# communication-hub.net
KiCad netlist of a schematic drawn in EAGLE
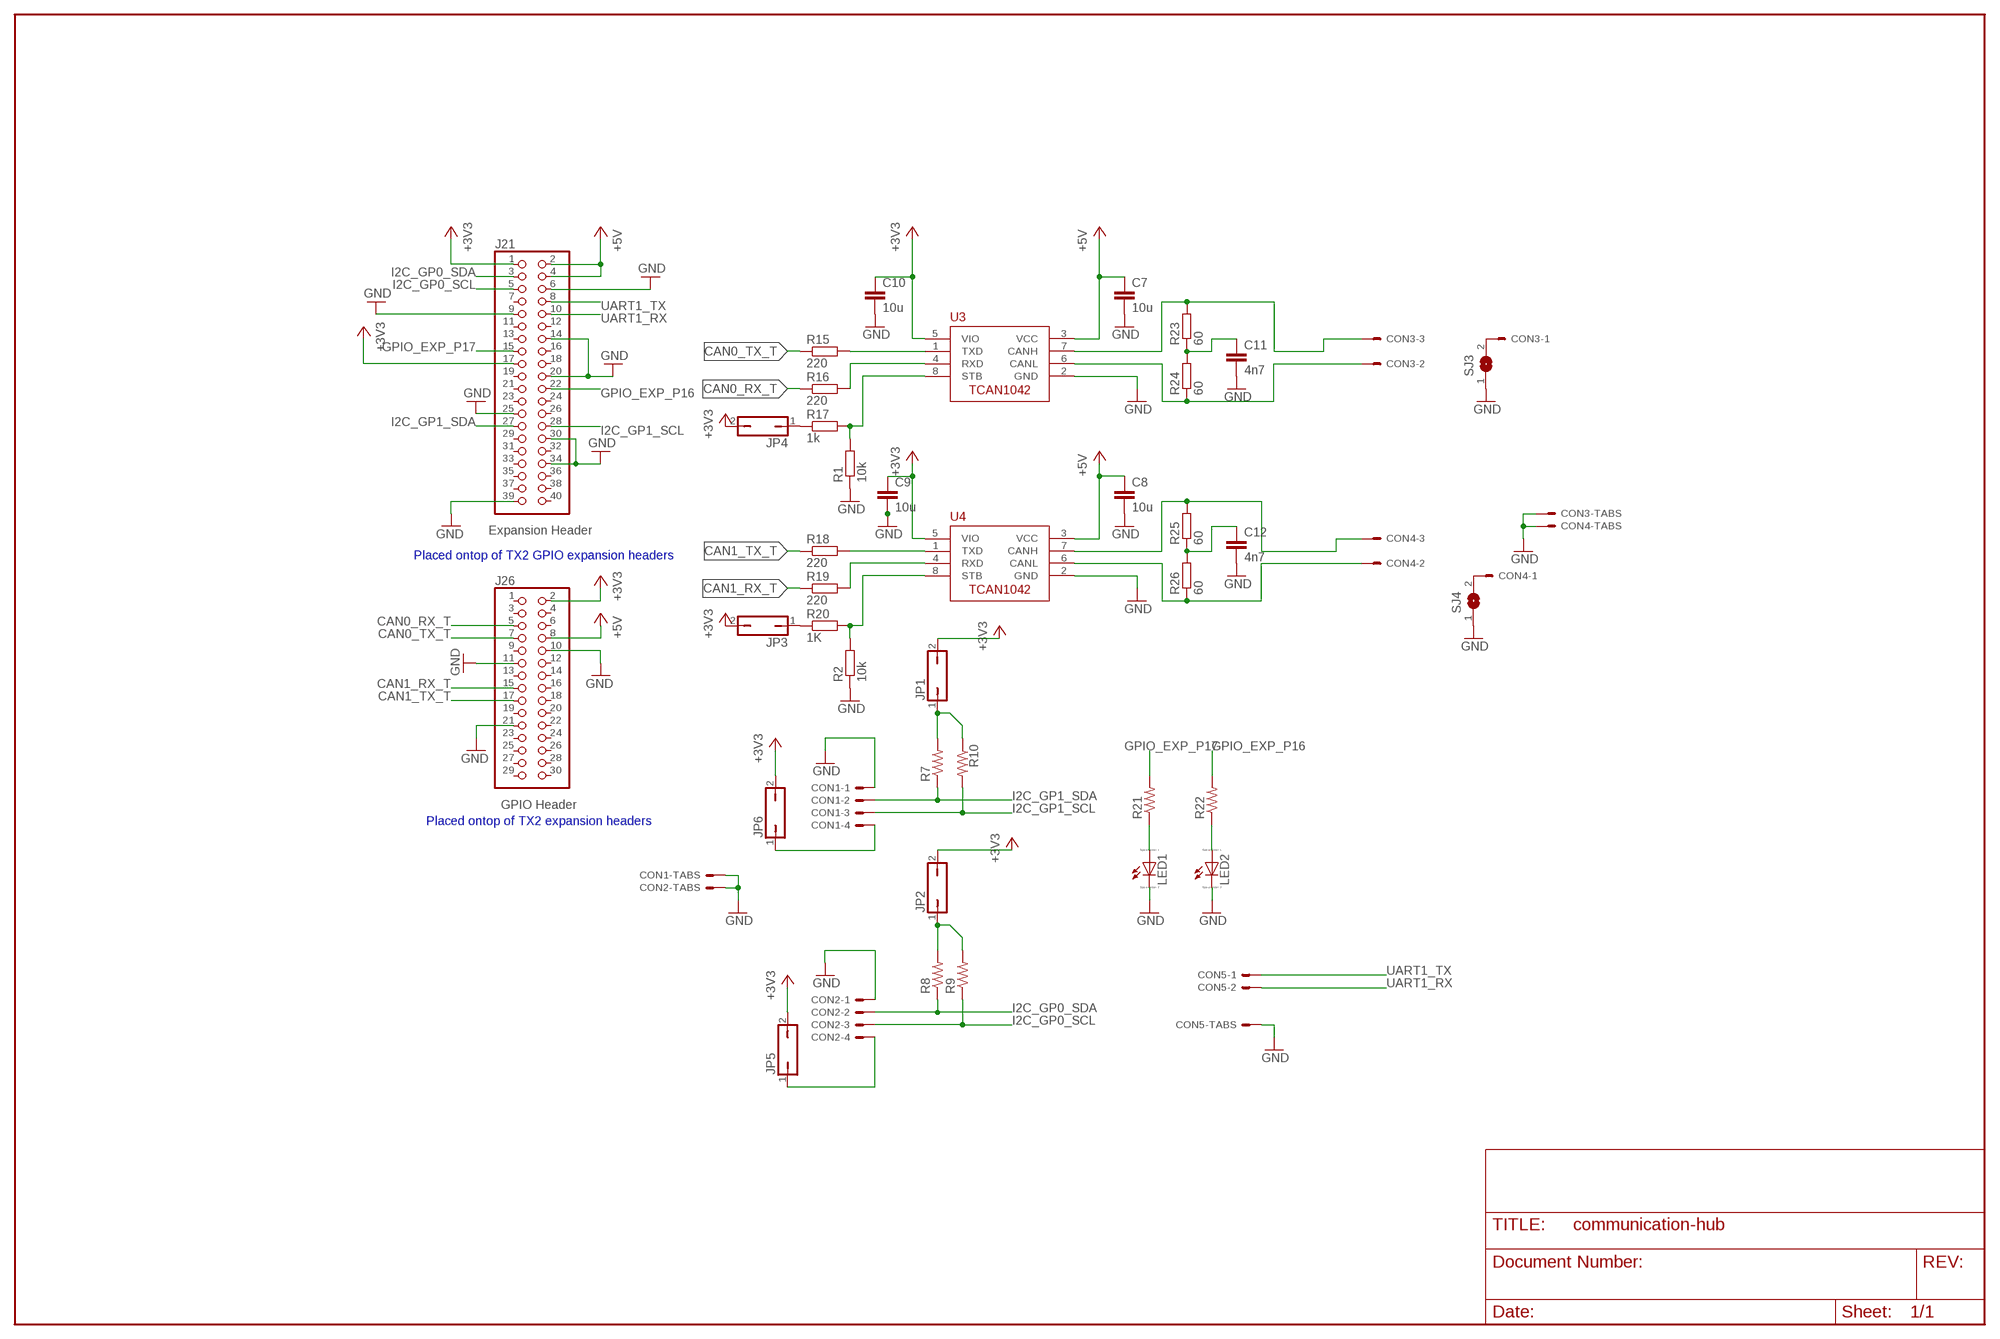
[diagram p0: schematic, sheet 1]

(export (version "E")
  (design (tool "Eeschema 10.0.6"))
  (components
    (comp (ref "C7")
      (value "10u")
      (footprint "eagle-import:C0805")
      (libsource (lib "eagle-import") (part "C-EUC0805"))
    )
    (comp (ref "C8")
      (value "10u")
      (footprint "eagle-import:C0805")
      (libsource (lib "eagle-import") (part "C-EUC0805"))
    )
    (comp (ref "C9")
      (value "10u")
      (footprint "eagle-import:C0805")
      (libsource (lib "eagle-import") (part "C-EUC0805"))
    )
    (comp (ref "C10")
      (value "10u")
      (footprint "eagle-import:C0805")
      (libsource (lib "eagle-import") (part "C-EUC0805"))
    )
    (comp (ref "C11")
      (value "4n7")
      (footprint "eagle-import:C0805")
      (libsource (lib "eagle-import") (part "C-EUC0805"))
    )
    (comp (ref "C12")
      (value "4n7")
      (footprint "eagle-import:C0805")
      (libsource (lib "eagle-import") (part "C-EUC0805"))
    )
    (comp (ref "CON1")
      (value "SM04B-GHS-TB")
      (footprint "eagle-import:SM04B-GHS-TB")
      (libsource (lib "eagle-import") (part "SM04B-GHS-TB"))
    )
    (comp (ref "CON2")
      (value "SM04B-GHS-TB")
      (footprint "eagle-import:SM04B-GHS-TB")
      (libsource (lib "eagle-import") (part "SM04B-GHS-TB"))
    )
    (comp (ref "CON3")
      (value "SM03B-GHS-TB")
      (footprint "eagle-import:SM03B-GHS-TB")
      (libsource (lib "eagle-import") (part "SM03B-GHS-TB"))
    )
    (comp (ref "CON4")
      (value "SM03B-GHS-TB")
      (footprint "eagle-import:SM03B-GHS-TB")
      (libsource (lib "eagle-import") (part "SM03B-GHS-TB"))
    )
    (comp (ref "CON5")
      (value "SM02B-GHS-TB")
      (footprint "eagle-import:SM02B-GHS-TB")
      (libsource (lib "eagle-import") (part "SM02B-GHS-TB"))
    )
    (comp (ref "J21")
      (value "PINHD-2X20")
      (footprint "eagle-import:2X20")
      (libsource (lib "eagle-import") (part "PINHD-2X20"))
    )
    (comp (ref "J26")
      (value "PINHD-2X15")
      (footprint "eagle-import:2X15")
      (libsource (lib "eagle-import") (part "PINHD-2X15"))
    )
    (comp (ref "JP1")
      (value "JP1Q")
      (footprint "eagle-import:JP1")
      (libsource (lib "eagle-import") (part "JP1Q"))
    )
    (comp (ref "JP2")
      (value "JP1Q")
      (footprint "eagle-import:JP1")
      (libsource (lib "eagle-import") (part "JP1Q"))
    )
    (comp (ref "JP3")
      (value "JP1Q")
      (footprint "eagle-import:JP1")
      (libsource (lib "eagle-import") (part "JP1Q"))
    )
    (comp (ref "JP4")
      (value "JP1Q")
      (footprint "eagle-import:JP1")
      (libsource (lib "eagle-import") (part "JP1Q"))
    )
    (comp (ref "JP5")
      (value "JP1Q")
      (footprint "eagle-import:JP1")
      (libsource (lib "eagle-import") (part "JP1Q"))
    )
    (comp (ref "JP6")
      (value "JP1Q")
      (footprint "eagle-import:JP1")
      (libsource (lib "eagle-import") (part "JP1Q"))
    )
    (comp (ref "LED1")
      (value "LED_E")
      (footprint "eagle-import:LED_1206")
      (libsource (lib "eagle-import") (part "LED_E"))
    )
    (comp (ref "LED2")
      (value "LED_E")
      (footprint "eagle-import:LED_1206")
      (libsource (lib "eagle-import") (part "LED_E"))
    )
    (comp (ref "R1")
      (value "10k")
      (footprint "eagle-import:R0805")
      (libsource (lib "eagle-import") (part "R-EU_R0805"))
    )
    (comp (ref "R2")
      (value "10k")
      (footprint "eagle-import:R0805")
      (libsource (lib "eagle-import") (part "R-EU_R0805"))
    )
    (comp (ref "R7")
      (value "R-US_M1206")
      (footprint "eagle-import:M1206")
      (libsource (lib "eagle-import") (part "R-US_M1206"))
    )
    (comp (ref "R8")
      (value "R-US_M1206")
      (footprint "eagle-import:M1206")
      (libsource (lib "eagle-import") (part "R-US_M1206"))
    )
    (comp (ref "R9")
      (value "R-US_M1206")
      (footprint "eagle-import:M1206")
      (libsource (lib "eagle-import") (part "R-US_M1206"))
    )
    (comp (ref "R10")
      (value "R-US_M1206")
      (footprint "eagle-import:M1206")
      (libsource (lib "eagle-import") (part "R-US_M1206"))
    )
    (comp (ref "R15")
      (value "220")
      (footprint "eagle-import:R0805")
      (libsource (lib "eagle-import") (part "R-EU_R0805"))
    )
    (comp (ref "R16")
      (value "220")
      (footprint "eagle-import:R0805")
      (libsource (lib "eagle-import") (part "R-EU_R0805"))
    )
    (comp (ref "R17")
      (value "1k")
      (footprint "eagle-import:R0805")
      (libsource (lib "eagle-import") (part "R-EU_R0805"))
    )
    (comp (ref "R18")
      (value "220")
      (footprint "eagle-import:R0805")
      (libsource (lib "eagle-import") (part "R-EU_R0805"))
    )
    (comp (ref "R19")
      (value "220")
      (footprint "eagle-import:R0805")
      (libsource (lib "eagle-import") (part "R-EU_R0805"))
    )
    (comp (ref "R20")
      (value "1K")
      (footprint "eagle-import:R0805")
      (libsource (lib "eagle-import") (part "R-EU_R0805"))
    )
    (comp (ref "R21")
      (value "R-US_M1206")
      (footprint "eagle-import:M1206")
      (libsource (lib "eagle-import") (part "R-US_M1206"))
    )
    (comp (ref "R22")
      (value "R-US_M1206")
      (footprint "eagle-import:M1206")
      (libsource (lib "eagle-import") (part "R-US_M1206"))
    )
    (comp (ref "R23")
      (value "60")
      (footprint "eagle-import:R1206")
      (libsource (lib "eagle-import") (part "R-EU_R1206"))
    )
    (comp (ref "R24")
      (value "60")
      (footprint "eagle-import:R1206")
      (libsource (lib "eagle-import") (part "R-EU_R1206"))
    )
    (comp (ref "R25")
      (value "60")
      (footprint "eagle-import:R1206")
      (libsource (lib "eagle-import") (part "R-EU_R1206"))
    )
    (comp (ref "R26")
      (value "60")
      (footprint "eagle-import:R1206")
      (libsource (lib "eagle-import") (part "R-EU_R1206"))
    )
    (comp (ref "SJ3") (value "SJ") (footprint "eagle-import:SJ") (libsource (lib "eagle-import") (part "SJ")))
    (comp (ref "SJ4") (value "SJ") (footprint "eagle-import:SJ") (libsource (lib "eagle-import") (part "SJ")))
    (comp (ref "U3")
      (value "TCAN1042HVDR")
      (footprint "eagle-import:SO-8")
      (libsource (lib "eagle-import") (part "TCAN1042HVDR"))
    )
    (comp (ref "U4")
      (value "TCAN1042HVDR")
      (footprint "eagle-import:SO-8")
      (libsource (lib "eagle-import") (part "TCAN1042HVDR"))
    )
  )
  (nets
    (net (code "1") (name "+3V3") (class "Default")
      (node (ref "C10") (pin "1") (pinfunction "1_1") (pintype "passive"))
      (node (ref "C9") (pin "1") (pinfunction "1_1") (pintype "passive"))
      (node (ref "J21") (pin "1") (pinfunction "1_1") (pintype "passive"))
      (node (ref "J21") (pin "17") (pinfunction "17_17") (pintype "passive"))
      (node (ref "J26") (pin "2") (pinfunction "2_2") (pintype "passive"))
      (node (ref "JP1") (pin "2") (pinfunction "2_2") (pintype "passive"))
      (node (ref "JP2") (pin "2") (pinfunction "2_2") (pintype "passive"))
      (node (ref "JP3") (pin "2") (pinfunction "2_2") (pintype "passive"))
      (node (ref "JP4") (pin "2") (pinfunction "2_2") (pintype "passive"))
      (node (ref "JP5") (pin "2") (pinfunction "2_2") (pintype "passive"))
      (node (ref "JP6") (pin "2") (pinfunction "2_2") (pintype "passive"))
      (node (ref "U3") (pin "5") (pinfunction "VIO_5") (pintype "bidirectional"))
      (node (ref "U4") (pin "5") (pinfunction "VIO_5") (pintype "bidirectional"))
    )
    (net (code "2") (name "+5V") (class "Default")
      (node (ref "C7") (pin "1") (pinfunction "1_1") (pintype "passive"))
      (node (ref "C8") (pin "1") (pinfunction "1_1") (pintype "passive"))
      (node (ref "J21") (pin "2") (pinfunction "2_2") (pintype "passive"))
      (node (ref "J21") (pin "4") (pinfunction "4_4") (pintype "passive"))
      (node (ref "J26") (pin "8") (pinfunction "8_8") (pintype "passive"))
      (node (ref "U3") (pin "3") (pinfunction "VCC_3") (pintype "bidirectional"))
      (node (ref "U4") (pin "3") (pinfunction "VCC_3") (pintype "bidirectional"))
    )
    (net (code "3") (name "/GPIO_EXP_P16") (class "Default")
      (node (ref "J21") (pin "22") (pinfunction "22_22") (pintype "passive"))
      (node (ref "R22") (pin "2") (pinfunction "2_2") (pintype "passive"))
    )
    (net (code "4") (name "/GPIO_EXP_P17") (class "Default")
      (node (ref "J21") (pin "15") (pinfunction "15_15") (pintype "passive"))
      (node (ref "R21") (pin "2") (pinfunction "2_2") (pintype "passive"))
    )
    (net (code "5") (name "/I2C_GP0_SCL") (class "Default")
      (node (ref "CON2") (pin "P$3") (pinfunction "S_P$3") (pintype "passive"))
      (node (ref "J21") (pin "5") (pinfunction "5_5") (pintype "passive"))
      (node (ref "R9") (pin "1") (pinfunction "1_1") (pintype "passive"))
    )
    (net (code "6") (name "/I2C_GP0_SDA") (class "Default")
      (node (ref "CON2") (pin "P$2") (pinfunction "S_P$2") (pintype "passive"))
      (node (ref "J21") (pin "3") (pinfunction "3_3") (pintype "passive"))
      (node (ref "R8") (pin "1") (pinfunction "1_1") (pintype "passive"))
    )
    (net (code "7") (name "/I2C_GP1_SCL") (class "Default")
      (node (ref "CON1") (pin "P$3") (pinfunction "S_P$3") (pintype "passive"))
      (node (ref "J21") (pin "28") (pinfunction "28_28") (pintype "passive"))
      (node (ref "R10") (pin "2") (pinfunction "2_2") (pintype "passive"))
    )
    (net (code "8") (name "/I2C_GP1_SDA") (class "Default")
      (node (ref "CON1") (pin "P$2") (pinfunction "S_P$2") (pintype "passive"))
      (node (ref "J21") (pin "27") (pinfunction "27_27") (pintype "passive"))
      (node (ref "R7") (pin "1") (pinfunction "1_1") (pintype "passive"))
    )
    (net (code "9") (name "/UART1_RX") (class "Default")
      (node (ref "CON5") (pin "P$2") (pinfunction "S_P$2") (pintype "passive"))
      (node (ref "J21") (pin "10") (pinfunction "10_10") (pintype "passive"))
    )
    (net (code "10") (name "/UART1_TX") (class "Default")
      (node (ref "CON5") (pin "P$1") (pinfunction "S_P$1") (pintype "passive"))
      (node (ref "J21") (pin "8") (pinfunction "8_8") (pintype "passive"))
    )
    (net (code "11") (name "CAN0_RX_T") (class "Default")
      (node (ref "J26") (pin "5") (pinfunction "5_5") (pintype "passive"))
      (node (ref "R16") (pin "1") (pinfunction "1_1") (pintype "passive"))
    )
    (net (code "12") (name "CAN0_TX_T") (class "Default")
      (node (ref "J26") (pin "7") (pinfunction "7_7") (pintype "passive"))
      (node (ref "R15") (pin "1") (pinfunction "1_1") (pintype "passive"))
    )
    (net (code "13") (name "CAN1_RX_T") (class "Default")
      (node (ref "J26") (pin "15") (pinfunction "15_15") (pintype "passive"))
      (node (ref "R19") (pin "1") (pinfunction "1_1") (pintype "passive"))
    )
    (net (code "14") (name "CAN1_TX_T") (class "Default")
      (node (ref "J26") (pin "17") (pinfunction "17_17") (pintype "passive"))
      (node (ref "R18") (pin "1") (pinfunction "1_1") (pintype "passive"))
    )
    (net (code "15") (name "GND") (class "Default")
      (node (ref "C10") (pin "2") (pinfunction "2_2") (pintype "passive"))
      (node (ref "C11") (pin "2") (pinfunction "2_2") (pintype "passive"))
      (node (ref "C12") (pin "2") (pinfunction "2_2") (pintype "passive"))
      (node (ref "C7") (pin "2") (pinfunction "2_2") (pintype "passive"))
      (node (ref "C8") (pin "2") (pinfunction "2_2") (pintype "passive"))
      (node (ref "C9") (pin "2") (pinfunction "2_2") (pintype "passive"))
      (node (ref "CON1") (pin "P$1") (pinfunction "S_P$1") (pintype "passive"))
      (node (ref "CON1") (pin "P$5") (pinfunction "S_P$5") (pintype "passive"))
      (node (ref "CON1") (pin "P$6") (pinfunction "S_P$6") (pintype "passive"))
      (node (ref "CON2") (pin "P$1") (pinfunction "S_P$1") (pintype "passive"))
      (node (ref "CON2") (pin "P$5") (pinfunction "S_P$5") (pintype "passive"))
      (node (ref "CON2") (pin "P$6") (pinfunction "S_P$6") (pintype "passive"))
      (node (ref "CON3") (pin "P$4") (pinfunction "S_P$4") (pintype "passive"))
      (node (ref "CON3") (pin "P$5") (pinfunction "S_P$5") (pintype "passive"))
      (node (ref "CON4") (pin "P$4") (pinfunction "S_P$4") (pintype "passive"))
      (node (ref "CON4") (pin "P$5") (pinfunction "S_P$5") (pintype "passive"))
      (node (ref "CON5") (pin "P$3") (pinfunction "S_P$3") (pintype "passive"))
      (node (ref "CON5") (pin "P$4") (pinfunction "S_P$4") (pintype "passive"))
      (node (ref "J21") (pin "14") (pinfunction "14_14") (pintype "passive"))
      (node (ref "J21") (pin "20") (pinfunction "20_20") (pintype "passive"))
      (node (ref "J21") (pin "25") (pinfunction "25_25") (pintype "passive"))
      (node (ref "J21") (pin "30") (pinfunction "30_30") (pintype "passive"))
      (node (ref "J21") (pin "34") (pinfunction "34_34") (pintype "passive"))
      (node (ref "J21") (pin "39") (pinfunction "39_39") (pintype "passive"))
      (node (ref "J21") (pin "6") (pinfunction "6_6") (pintype "passive"))
      (node (ref "J21") (pin "9") (pinfunction "9_9") (pintype "passive"))
      (node (ref "J26") (pin "10") (pinfunction "10_10") (pintype "passive"))
      (node (ref "J26") (pin "11") (pinfunction "11_11") (pintype "passive"))
      (node (ref "J26") (pin "21") (pinfunction "21_21") (pintype "passive"))
      (node (ref "LED1") (pin "C") (pinfunction "C_C") (pintype "passive"))
      (node (ref "LED2") (pin "C") (pinfunction "C_C") (pintype "passive"))
      (node (ref "R1") (pin "1") (pinfunction "1_1") (pintype "passive"))
      (node (ref "R2") (pin "1") (pinfunction "1_1") (pintype "passive"))
      (node (ref "SJ3") (pin "1") (pinfunction "1_1") (pintype "passive"))
      (node (ref "SJ4") (pin "1") (pinfunction "1_1") (pintype "passive"))
      (node (ref "U3") (pin "2") (pinfunction "GND_2") (pintype "bidirectional"))
      (node (ref "U4") (pin "2") (pinfunction "GND_2") (pintype "bidirectional"))
    )
    (net (code "16") (name "Net-(C11-Pad1)") (class "Default")
      (node (ref "C11") (pin "1") (pinfunction "1_1") (pintype "passive"))
      (node (ref "R23") (pin "1") (pinfunction "1_1") (pintype "passive"))
      (node (ref "R24") (pin "2") (pinfunction "2_2") (pintype "passive"))
    )
    (net (code "17") (name "Net-(C12-Pad1)") (class "Default")
      (node (ref "C12") (pin "1") (pinfunction "1_1") (pintype "passive"))
      (node (ref "R25") (pin "1") (pinfunction "1_1") (pintype "passive"))
      (node (ref "R26") (pin "2") (pinfunction "2_2") (pintype "passive"))
    )
    (net (code "18") (name "Net-(CON1D-S)") (class "Default")
      (node (ref "CON1") (pin "P$4") (pinfunction "S_P$4") (pintype "passive"))
      (node (ref "JP6") (pin "1") (pinfunction "1_1") (pintype "passive"))
    )
    (net (code "19") (name "Net-(CON2D-S)") (class "Default")
      (node (ref "CON2") (pin "P$4") (pinfunction "S_P$4") (pintype "passive"))
      (node (ref "JP5") (pin "1") (pinfunction "1_1") (pintype "passive"))
    )
    (net (code "20") (name "Net-(CON3A-S)") (class "Default")
      (node (ref "CON3") (pin "P$1") (pinfunction "S_P$1") (pintype "passive"))
      (node (ref "SJ3") (pin "2") (pinfunction "2_2") (pintype "passive"))
    )
    (net (code "21") (name "Net-(CON3B-S)") (class "Default")
      (node (ref "CON3") (pin "P$2") (pinfunction "S_P$2") (pintype "passive"))
      (node (ref "R24") (pin "1") (pinfunction "1_1") (pintype "passive"))
      (node (ref "U3") (pin "6") (pinfunction "CANL_6") (pintype "bidirectional"))
    )
    (net (code "22") (name "Net-(CON3C-S)") (class "Default")
      (node (ref "CON3") (pin "P$3") (pinfunction "S_P$3") (pintype "passive"))
      (node (ref "R23") (pin "2") (pinfunction "2_2") (pintype "passive"))
      (node (ref "U3") (pin "7") (pinfunction "CANH_7") (pintype "bidirectional"))
    )
    (net (code "23") (name "Net-(CON4A-S)") (class "Default")
      (node (ref "CON4") (pin "P$1") (pinfunction "S_P$1") (pintype "passive"))
      (node (ref "SJ4") (pin "2") (pinfunction "2_2") (pintype "passive"))
    )
    (net (code "24") (name "Net-(CON4B-S)") (class "Default")
      (node (ref "CON4") (pin "P$2") (pinfunction "S_P$2") (pintype "passive"))
      (node (ref "R26") (pin "1") (pinfunction "1_1") (pintype "passive"))
      (node (ref "U4") (pin "6") (pinfunction "CANL_6") (pintype "bidirectional"))
    )
    (net (code "25") (name "Net-(CON4C-S)") (class "Default")
      (node (ref "CON4") (pin "P$3") (pinfunction "S_P$3") (pintype "passive"))
      (node (ref "R25") (pin "2") (pinfunction "2_2") (pintype "passive"))
      (node (ref "U4") (pin "7") (pinfunction "CANH_7") (pintype "bidirectional"))
    )
    (net (code "26") (name "Net-(JP1-Pad1)") (class "Default")
      (node (ref "JP1") (pin "1") (pinfunction "1_1") (pintype "passive"))
      (node (ref "R10") (pin "1") (pinfunction "1_1") (pintype "passive"))
      (node (ref "R7") (pin "2") (pinfunction "2_2") (pintype "passive"))
    )
    (net (code "27") (name "Net-(JP2-Pad1)") (class "Default")
      (node (ref "JP2") (pin "1") (pinfunction "1_1") (pintype "passive"))
      (node (ref "R8") (pin "2") (pinfunction "2_2") (pintype "passive"))
      (node (ref "R9") (pin "2") (pinfunction "2_2") (pintype "passive"))
    )
    (net (code "28") (name "Net-(JP3-Pad1)") (class "Default")
      (node (ref "JP3") (pin "1") (pinfunction "1_1") (pintype "passive"))
      (node (ref "R20") (pin "1") (pinfunction "1_1") (pintype "passive"))
    )
    (net (code "29") (name "Net-(JP4-Pad1)") (class "Default")
      (node (ref "JP4") (pin "1") (pinfunction "1_1") (pintype "passive"))
      (node (ref "R17") (pin "1") (pinfunction "1_1") (pintype "passive"))
    )
    (net (code "30") (name "Net-(LED1-PadA)") (class "Default")
      (node (ref "LED1") (pin "A") (pinfunction "A_A") (pintype "passive"))
      (node (ref "R21") (pin "1") (pinfunction "1_1") (pintype "passive"))
    )
    (net (code "31") (name "Net-(LED2-PadA)") (class "Default")
      (node (ref "LED2") (pin "A") (pinfunction "A_A") (pintype "passive"))
      (node (ref "R22") (pin "1") (pinfunction "1_1") (pintype "passive"))
    )
    (net (code "32") (name "Net-(U3-RXD)") (class "Default")
      (node (ref "R16") (pin "2") (pinfunction "2_2") (pintype "passive"))
      (node (ref "U3") (pin "4") (pinfunction "RXD_4") (pintype "bidirectional"))
    )
    (net (code "33") (name "Net-(U3-STB)") (class "Default")
      (node (ref "R1") (pin "2") (pinfunction "2_2") (pintype "passive"))
      (node (ref "R17") (pin "2") (pinfunction "2_2") (pintype "passive"))
      (node (ref "U3") (pin "8") (pinfunction "STB_8") (pintype "bidirectional"))
    )
    (net (code "34") (name "Net-(U3-TXD)") (class "Default")
      (node (ref "R15") (pin "2") (pinfunction "2_2") (pintype "passive"))
      (node (ref "U3") (pin "1") (pinfunction "TXD_1") (pintype "bidirectional"))
    )
    (net (code "35") (name "Net-(U4-RXD)") (class "Default")
      (node (ref "R19") (pin "2") (pinfunction "2_2") (pintype "passive"))
      (node (ref "U4") (pin "4") (pinfunction "RXD_4") (pintype "bidirectional"))
    )
    (net (code "36") (name "Net-(U4-STB)") (class "Default")
      (node (ref "R2") (pin "2") (pinfunction "2_2") (pintype "passive"))
      (node (ref "R20") (pin "2") (pinfunction "2_2") (pintype "passive"))
      (node (ref "U4") (pin "8") (pinfunction "STB_8") (pintype "bidirectional"))
    )
    (net (code "37") (name "Net-(U4-TXD)") (class "Default")
      (node (ref "R18") (pin "2") (pinfunction "2_2") (pintype "passive"))
      (node (ref "U4") (pin "1") (pinfunction "TXD_1") (pintype "bidirectional"))
    )
    (net (code "38") (name "unconnected-(J21-Pad7)") (class "Default")
      (node (ref "J21") (pin "7") (pinfunction "7_7") (pintype "passive"))
    )
    (net (code "39") (name "unconnected-(J21-Pad11)") (class "Default")
      (node (ref "J21") (pin "11") (pinfunction "11_11") (pintype "passive"))
    )
    (net (code "40") (name "unconnected-(J21-Pad12)") (class "Default")
      (node (ref "J21") (pin "12") (pinfunction "12_12") (pintype "passive"))
    )
    (net (code "41") (name "unconnected-(J21-Pad13)") (class "Default")
      (node (ref "J21") (pin "13") (pinfunction "13_13") (pintype "passive"))
    )
    (net (code "42") (name "unconnected-(J21-Pad16)") (class "Default")
      (node (ref "J21") (pin "16") (pinfunction "16_16") (pintype "passive"))
    )
    (net (code "43") (name "unconnected-(J21-Pad18)") (class "Default")
      (node (ref "J21") (pin "18") (pinfunction "18_18") (pintype "passive"))
    )
    (net (code "44") (name "unconnected-(J21-Pad19)") (class "Default")
      (node (ref "J21") (pin "19") (pinfunction "19_19") (pintype "passive"))
    )
    (net (code "45") (name "unconnected-(J21-Pad21)") (class "Default")
      (node (ref "J21") (pin "21") (pinfunction "21_21") (pintype "passive"))
    )
    (net (code "46") (name "unconnected-(J21-Pad23)") (class "Default")
      (node (ref "J21") (pin "23") (pinfunction "23_23") (pintype "passive"))
    )
    (net (code "47") (name "unconnected-(J21-Pad24)") (class "Default")
      (node (ref "J21") (pin "24") (pinfunction "24_24") (pintype "passive"))
    )
    (net (code "48") (name "unconnected-(J21-Pad26)") (class "Default")
      (node (ref "J21") (pin "26") (pinfunction "26_26") (pintype "passive"))
    )
    (net (code "49") (name "unconnected-(J21-Pad29)") (class "Default")
      (node (ref "J21") (pin "29") (pinfunction "29_29") (pintype "passive"))
    )
    (net (code "50") (name "unconnected-(J21-Pad31)") (class "Default")
      (node (ref "J21") (pin "31") (pinfunction "31_31") (pintype "passive"))
    )
    (net (code "51") (name "unconnected-(J21-Pad32)") (class "Default")
      (node (ref "J21") (pin "32") (pinfunction "32_32") (pintype "passive"))
    )
    (net (code "52") (name "unconnected-(J21-Pad33)") (class "Default")
      (node (ref "J21") (pin "33") (pinfunction "33_33") (pintype "passive"))
    )
    (net (code "53") (name "unconnected-(J21-Pad35)") (class "Default")
      (node (ref "J21") (pin "35") (pinfunction "35_35") (pintype "passive"))
    )
    (net (code "54") (name "unconnected-(J21-Pad36)") (class "Default")
      (node (ref "J21") (pin "36") (pinfunction "36_36") (pintype "passive"))
    )
    (net (code "55") (name "unconnected-(J21-Pad37)") (class "Default")
      (node (ref "J21") (pin "37") (pinfunction "37_37") (pintype "passive"))
    )
    (net (code "56") (name "unconnected-(J21-Pad38)") (class "Default")
      (node (ref "J21") (pin "38") (pinfunction "38_38") (pintype "passive"))
    )
    (net (code "57") (name "unconnected-(J21-Pad40)") (class "Default")
      (node (ref "J21") (pin "40") (pinfunction "40_40") (pintype "passive"))
    )
    (net (code "58") (name "unconnected-(J26-Pad1)") (class "Default")
      (node (ref "J26") (pin "1") (pinfunction "1_1") (pintype "passive"))
    )
    (net (code "59") (name "unconnected-(J26-Pad3)") (class "Default")
      (node (ref "J26") (pin "3") (pinfunction "3_3") (pintype "passive"))
    )
    (net (code "60") (name "unconnected-(J26-Pad4)") (class "Default")
      (node (ref "J26") (pin "4") (pinfunction "4_4") (pintype "passive"))
    )
    (net (code "61") (name "unconnected-(J26-Pad6)") (class "Default")
      (node (ref "J26") (pin "6") (pinfunction "6_6") (pintype "passive"))
    )
    (net (code "62") (name "unconnected-(J26-Pad9)") (class "Default")
      (node (ref "J26") (pin "9") (pinfunction "9_9") (pintype "passive"))
    )
    (net (code "63") (name "unconnected-(J26-Pad12)") (class "Default")
      (node (ref "J26") (pin "12") (pinfunction "12_12") (pintype "passive"))
    )
    (net (code "64") (name "unconnected-(J26-Pad13)") (class "Default")
      (node (ref "J26") (pin "13") (pinfunction "13_13") (pintype "passive"))
    )
    (net (code "65") (name "unconnected-(J26-Pad14)") (class "Default")
      (node (ref "J26") (pin "14") (pinfunction "14_14") (pintype "passive"))
    )
    (net (code "66") (name "unconnected-(J26-Pad16)") (class "Default")
      (node (ref "J26") (pin "16") (pinfunction "16_16") (pintype "passive"))
    )
    (net (code "67") (name "unconnected-(J26-Pad18)") (class "Default")
      (node (ref "J26") (pin "18") (pinfunction "18_18") (pintype "passive"))
    )
    (net (code "68") (name "unconnected-(J26-Pad19)") (class "Default")
      (node (ref "J26") (pin "19") (pinfunction "19_19") (pintype "passive"))
    )
    (net (code "69") (name "unconnected-(J26-Pad20)") (class "Default")
      (node (ref "J26") (pin "20") (pinfunction "20_20") (pintype "passive"))
    )
    (net (code "70") (name "unconnected-(J26-Pad22)") (class "Default")
      (node (ref "J26") (pin "22") (pinfunction "22_22") (pintype "passive"))
    )
    (net (code "71") (name "unconnected-(J26-Pad23)") (class "Default")
      (node (ref "J26") (pin "23") (pinfunction "23_23") (pintype "passive"))
    )
    (net (code "72") (name "unconnected-(J26-Pad24)") (class "Default")
      (node (ref "J26") (pin "24") (pinfunction "24_24") (pintype "passive"))
    )
    (net (code "73") (name "unconnected-(J26-Pad25)") (class "Default")
      (node (ref "J26") (pin "25") (pinfunction "25_25") (pintype "passive"))
    )
    (net (code "74") (name "unconnected-(J26-Pad26)") (class "Default")
      (node (ref "J26") (pin "26") (pinfunction "26_26") (pintype "passive"))
    )
    (net (code "75") (name "unconnected-(J26-Pad27)") (class "Default")
      (node (ref "J26") (pin "27") (pinfunction "27_27") (pintype "passive"))
    )
    (net (code "76") (name "unconnected-(J26-Pad28)") (class "Default")
      (node (ref "J26") (pin "28") (pinfunction "28_28") (pintype "passive"))
    )
    (net (code "77") (name "unconnected-(J26-Pad29)") (class "Default")
      (node (ref "J26") (pin "29") (pinfunction "29_29") (pintype "passive"))
    )
    (net (code "78") (name "unconnected-(J26-Pad30)") (class "Default")
      (node (ref "J26") (pin "30") (pinfunction "30_30") (pintype "passive"))
    )
  )
)
